# DAC_Test_PCB.net
KiCad netlist of a schematic drawn in EAGLE
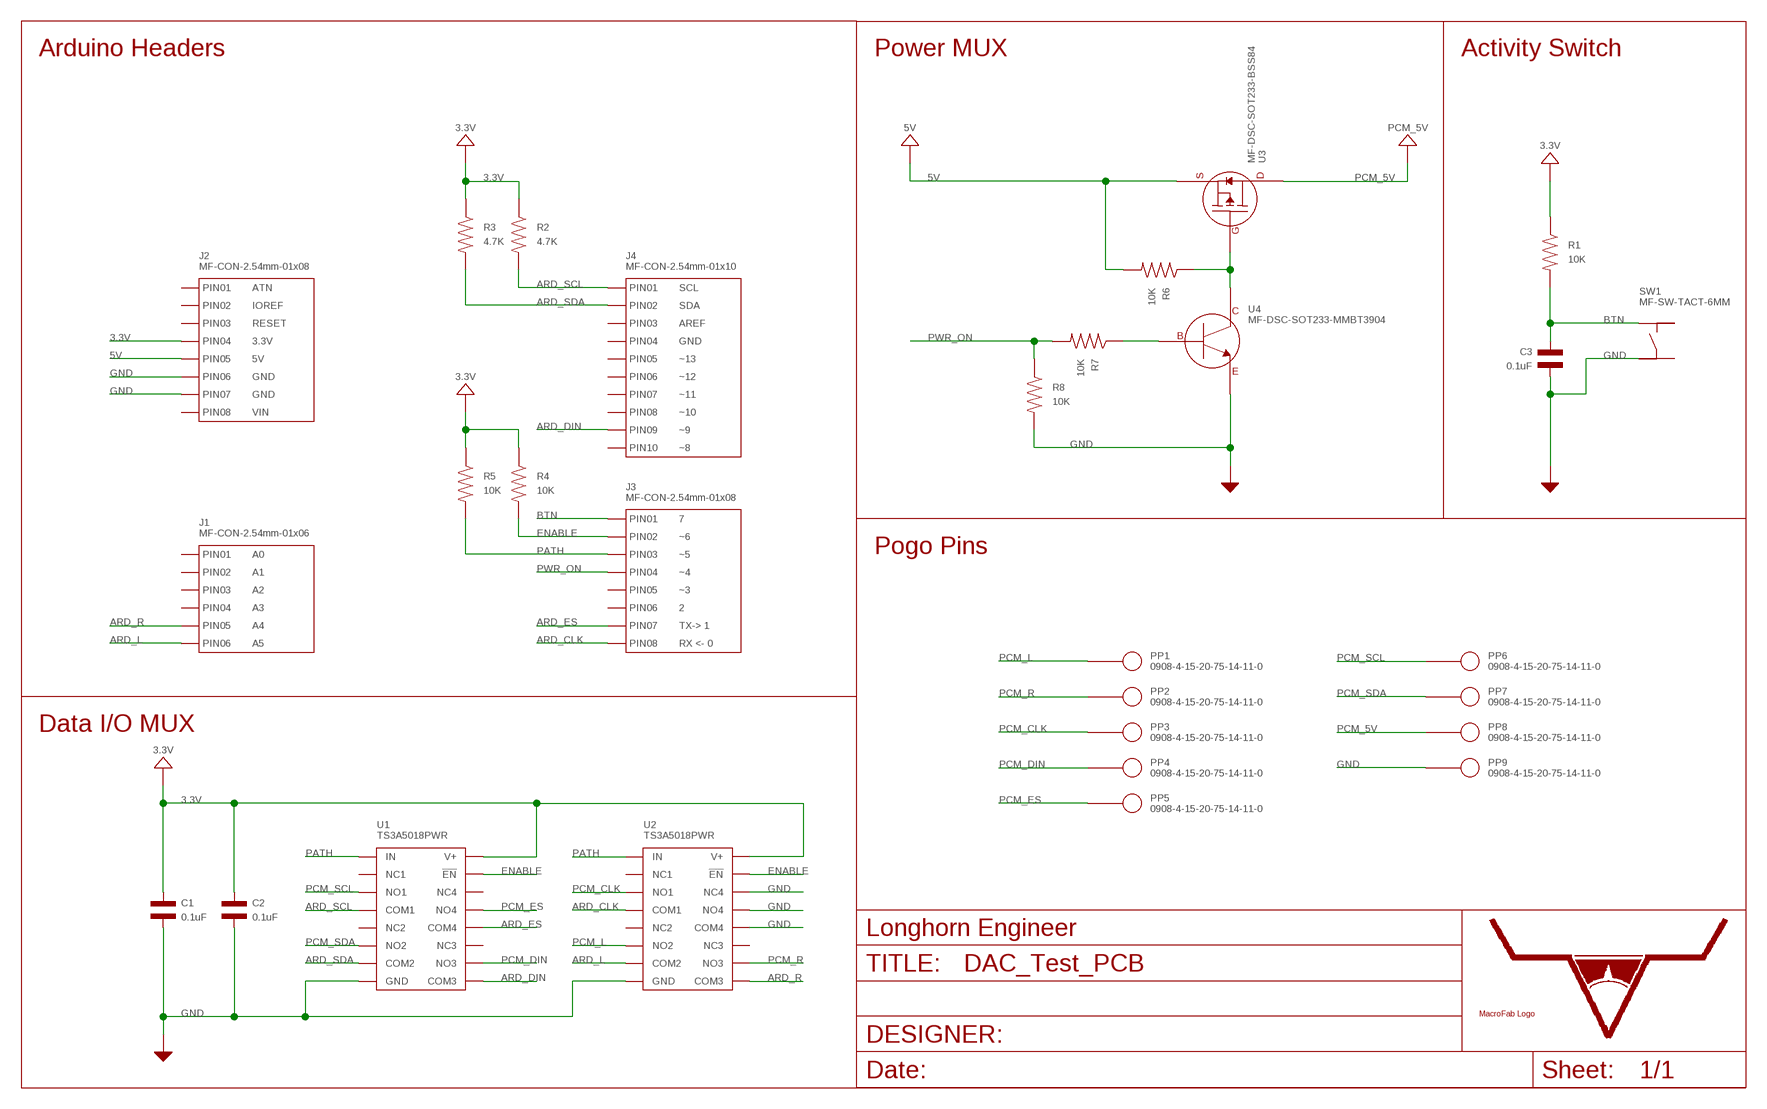
[diagram p0: schematic, sheet 1]

(export (version "E")
  (design (tool "Eeschema 10.0.6"))
  (components
    (comp (ref "C1")
      (value "0.1uF")
      (footprint "eagle-import:C0603")
      (libsource (lib "eagle-import") (part "CAPACITOR_NP_0603"))
    )
    (comp (ref "C2")
      (value "0.1uF")
      (footprint "eagle-import:C0603")
      (libsource (lib "eagle-import") (part "CAPACITOR_NP_0603"))
    )
    (comp (ref "C3")
      (value "0.1uF")
      (footprint "eagle-import:C0603")
      (libsource (lib "eagle-import") (part "CAPACITOR_NP_0603"))
    )
    (comp (ref "J1")
      (value "MF-CON-2.54mm-01x06")
      (footprint "eagle-import:PTH_2.54MM_01X06")
      (fields
        (field (name "HOUSEPART") "YES")
        (field (name "LABEL01") "A0")
        (field (name "LABEL02") "A1")
        (field (name "LABEL03") "A2")
        (field (name "LABEL04") "A3")
        (field (name "LABEL05") "A4")
        (field (name "LABEL06") "A5")
      )
      (libsource (lib "eagle-import") (part "CON_01X06_PTH_2.54MM"))
    )
    (comp (ref "J2")
      (value "MF-CON-2.54mm-01x08")
      (footprint "eagle-import:PTH_2.54MM_01X08")
      (fields
        (field (name "HOUSEPART") "YES")
        (field (name "LABEL01") "ATN")
        (field (name "LABEL02") "IOREF")
        (field (name "LABEL03") "RESET")
        (field (name "LABEL04") "3.3V")
        (field (name "LABEL05") "5V")
        (field (name "LABEL06") "GND")
        (field (name "LABEL07") "GND")
        (field (name "LABEL08") "VIN")
      )
      (libsource (lib "eagle-import") (part "CON_01X08_PTH_2.54MM"))
    )
    (comp (ref "J3")
      (value "MF-CON-2.54mm-01x08")
      (footprint "eagle-import:PTH_2.54MM_01X08")
      (fields
        (field (name "HOUSEPART") "YES")
        (field (name "LABEL01") "7")
        (field (name "LABEL02") "~6")
        (field (name "LABEL03") "~5")
        (field (name "LABEL04") "~4")
        (field (name "LABEL05") "~3")
        (field (name "LABEL06") "2")
        (field (name "LABEL07") "TX-> 1")
        (field (name "LABEL08") "RX <- 0")
      )
      (libsource (lib "eagle-import") (part "CON_01X08_PTH_2.54MM"))
    )
    (comp (ref "J4")
      (value "MF-CON-2.54mm-01x10")
      (footprint "eagle-import:PTH_2.54MM_01X10")
      (fields
        (field (name "HOUSEPART") "YES")
        (field (name "LABEL01") "SCL")
        (field (name "LABEL02") "SDA")
        (field (name "LABEL03") "AREF")
        (field (name "LABEL04") "GND")
        (field (name "LABEL05") "~13")
        (field (name "LABEL06") "~12")
        (field (name "LABEL07") "~11")
        (field (name "LABEL08") "~10")
        (field (name "LABEL09") "~9")
        (field (name "LABEL10") "~8")
      )
      (libsource (lib "eagle-import") (part "CON_01X10_PTH_2.54MM"))
    )
    (comp (ref "PP1")
      (value "0908-4-15-20-75-14-11-0")
      (footprint "eagle-import:0908-4-15-20-75-14-11-0")
      (libsource (lib "eagle-import") (part "POGO_PIN_0908-4-15-20-75-14-11-0"))
    )
    (comp (ref "PP2")
      (value "0908-4-15-20-75-14-11-0")
      (footprint "eagle-import:0908-4-15-20-75-14-11-0")
      (libsource (lib "eagle-import") (part "POGO_PIN_0908-4-15-20-75-14-11-0"))
    )
    (comp (ref "PP3")
      (value "0908-4-15-20-75-14-11-0")
      (footprint "eagle-import:0908-4-15-20-75-14-11-0")
      (libsource (lib "eagle-import") (part "POGO_PIN_0908-4-15-20-75-14-11-0"))
    )
    (comp (ref "PP4")
      (value "0908-4-15-20-75-14-11-0")
      (footprint "eagle-import:0908-4-15-20-75-14-11-0")
      (libsource (lib "eagle-import") (part "POGO_PIN_0908-4-15-20-75-14-11-0"))
    )
    (comp (ref "PP5")
      (value "0908-4-15-20-75-14-11-0")
      (footprint "eagle-import:0908-4-15-20-75-14-11-0")
      (libsource (lib "eagle-import") (part "POGO_PIN_0908-4-15-20-75-14-11-0"))
    )
    (comp (ref "PP6")
      (value "0908-4-15-20-75-14-11-0")
      (footprint "eagle-import:0908-4-15-20-75-14-11-0")
      (libsource (lib "eagle-import") (part "POGO_PIN_0908-4-15-20-75-14-11-0"))
    )
    (comp (ref "PP7")
      (value "0908-4-15-20-75-14-11-0")
      (footprint "eagle-import:0908-4-15-20-75-14-11-0")
      (libsource (lib "eagle-import") (part "POGO_PIN_0908-4-15-20-75-14-11-0"))
    )
    (comp (ref "PP8")
      (value "0908-4-15-20-75-14-11-0")
      (footprint "eagle-import:0908-4-15-20-75-14-11-0")
      (libsource (lib "eagle-import") (part "POGO_PIN_0908-4-15-20-75-14-11-0"))
    )
    (comp (ref "PP9")
      (value "0908-4-15-20-75-14-11-0")
      (footprint "eagle-import:0908-4-15-20-75-14-11-0")
      (libsource (lib "eagle-import") (part "POGO_PIN_0908-4-15-20-75-14-11-0"))
    )
    (comp (ref "R1")
      (value "10K")
      (footprint "eagle-import:R0603")
      (libsource (lib "eagle-import") (part "RESISTOR_0603"))
    )
    (comp (ref "R2")
      (value "4.7K")
      (footprint "eagle-import:R0603")
      (libsource (lib "eagle-import") (part "RESISTOR_0603"))
    )
    (comp (ref "R3")
      (value "4.7K")
      (footprint "eagle-import:R0603")
      (libsource (lib "eagle-import") (part "RESISTOR_0603"))
    )
    (comp (ref "R4")
      (value "10K")
      (footprint "eagle-import:R0603")
      (libsource (lib "eagle-import") (part "RESISTOR_0603"))
    )
    (comp (ref "R5")
      (value "10K")
      (footprint "eagle-import:R0603")
      (libsource (lib "eagle-import") (part "RESISTOR_0603"))
    )
    (comp (ref "R6")
      (value "10K")
      (footprint "eagle-import:R0603")
      (libsource (lib "eagle-import") (part "RESISTOR_0603"))
    )
    (comp (ref "R7")
      (value "10K")
      (footprint "eagle-import:R0603")
      (libsource (lib "eagle-import") (part "RESISTOR_0603"))
    )
    (comp (ref "R8")
      (value "10K")
      (footprint "eagle-import:R0603")
      (libsource (lib "eagle-import") (part "RESISTOR_0603"))
    )
    (comp (ref "SW1")
      (value "MF-SW-TACT-6MM")
      (footprint "eagle-import:TACT6MM")
      (fields (field (name "HOUSEPART") "YES"))
      (libsource (lib "eagle-import") (part "TACT_6MM"))
    )
    (comp (ref "U$8")
      (value "LHE_FRAME")
      (footprint "eagle-import:LHE_FRAME")
      (fields (field (name "DNAME") "Parker Dillmann") (field (name "REVNUM") "REV 1"))
      (libsource (lib "eagle-import") (part "LHE_FRAME"))
    )
    (comp (ref "U$9")
      (value "MF_LOGOLOGO_MEDIUM")
      (footprint "eagle-import:MF_LOGO_MEDIUM")
      (libsource (lib "eagle-import") (part "MF_LOGOLOGO_MEDIUM"))
    )
    (comp (ref "U1")
      (value "TS3A5018PWR")
      (footprint "eagle-import:TS3A5018_TTSOP-16")
      (libsource (lib "eagle-import") (part "TS3A5018PWR"))
    )
    (comp (ref "U2")
      (value "TS3A5018PWR")
      (footprint "eagle-import:TS3A5018_TTSOP-16")
      (libsource (lib "eagle-import") (part "TS3A5018PWR"))
    )
    (comp (ref "U3")
      (value "MF-DSC-SOT233-BSS84")
      (footprint "eagle-import:SOT-23-3")
      (fields (field (name "HOUSEPART") "YES"))
      (libsource (lib "eagle-import") (part "P-CHANNEL_FET_SOT-23-3_BSS84"))
    )
    (comp (ref "U4")
      (value "MF-DSC-SOT233-MMBT3904")
      (footprint "eagle-import:SOT-23-3")
      (fields (field (name "HOUSEPART") "YES"))
      (libsource (lib "eagle-import") (part "NPN_BJT_SOT-23-3MMBT3904"))
    )
  )
  (nets
    (net (code "1") (name "/ARD_CLK") (class "Default")
      (node (ref "J3") (pin "P$8") (pinfunction "PIN8_P$8") (pintype "bidirectional"))
      (node (ref "U2") (pin "4") (pinfunction "COM1_4") (pintype "bidirectional"))
    )
    (net (code "2") (name "/ARD_DIN") (class "Default")
      (node (ref "J4") (pin "P$9") (pinfunction "PIN9_P$9") (pintype "bidirectional"))
      (node (ref "U1") (pin "9") (pinfunction "COM3_9") (pintype "bidirectional"))
    )
    (net (code "3") (name "/ARD_ES") (class "Default")
      (node (ref "J3") (pin "P$7") (pinfunction "PIN7_P$7") (pintype "bidirectional"))
      (node (ref "U1") (pin "12") (pinfunction "COM4_12") (pintype "bidirectional"))
    )
    (net (code "4") (name "/ARD_L") (class "Default")
      (node (ref "J1") (pin "P$6") (pinfunction "PIN6_P$6") (pintype "bidirectional"))
      (node (ref "U2") (pin "7") (pinfunction "COM2_7") (pintype "bidirectional"))
    )
    (net (code "5") (name "/ARD_R") (class "Default")
      (node (ref "J1") (pin "P$5") (pinfunction "PIN5_P$5") (pintype "bidirectional"))
      (node (ref "U2") (pin "9") (pinfunction "COM3_9") (pintype "bidirectional"))
    )
    (net (code "6") (name "/ARD_SCL") (class "Default")
      (node (ref "J4") (pin "P$1") (pinfunction "PIN1_P$1") (pintype "bidirectional"))
      (node (ref "R2") (pin "P$2") (pinfunction "P$2_P$2") (pintype "passive"))
      (node (ref "U1") (pin "4") (pinfunction "COM1_4") (pintype "bidirectional"))
    )
    (net (code "7") (name "/ARD_SDA") (class "Default")
      (node (ref "J4") (pin "P$2") (pinfunction "PIN2_P$2") (pintype "bidirectional"))
      (node (ref "R3") (pin "P$2") (pinfunction "P$2_P$2") (pintype "passive"))
      (node (ref "U1") (pin "7") (pinfunction "COM2_7") (pintype "bidirectional"))
    )
    (net (code "8") (name "/BTN") (class "Default")
      (node (ref "C3") (pin "P$1") (pinfunction "P$1_P$1") (pintype "passive"))
      (node (ref "J3") (pin "P$1") (pinfunction "PIN1_P$1") (pintype "bidirectional"))
      (node (ref "R1") (pin "P$2") (pinfunction "P$2_P$2") (pintype "passive"))
      (node (ref "SW1") (pin "P$1") (pinfunction "P$1_P$1") (pintype "bidirectional"))
    )
    (net (code "9") (name "/ENABLE") (class "Default")
      (node (ref "J3") (pin "P$2") (pinfunction "PIN2_P$2") (pintype "bidirectional"))
      (node (ref "R4") (pin "P$2") (pinfunction "P$2_P$2") (pintype "passive"))
      (node (ref "U1") (pin "15") (pinfunction "EN'_15") (pintype "bidirectional"))
      (node (ref "U2") (pin "15") (pinfunction "EN'_15") (pintype "bidirectional"))
    )
    (net (code "10") (name "/PATH") (class "Default")
      (node (ref "J3") (pin "P$3") (pinfunction "PIN3_P$3") (pintype "bidirectional"))
      (node (ref "R5") (pin "P$2") (pinfunction "P$2_P$2") (pintype "passive"))
      (node (ref "U1") (pin "1") (pinfunction "IN_1") (pintype "bidirectional"))
      (node (ref "U2") (pin "1") (pinfunction "IN_1") (pintype "bidirectional"))
    )
    (net (code "11") (name "/PCM_CLK") (class "Default")
      (node (ref "PP3") (pin "P$1") (pinfunction "P$1_P$1") (pintype "bidirectional"))
      (node (ref "U2") (pin "3") (pinfunction "NO1_3") (pintype "bidirectional"))
    )
    (net (code "12") (name "/PCM_DIN") (class "Default")
      (node (ref "PP4") (pin "P$1") (pinfunction "P$1_P$1") (pintype "bidirectional"))
      (node (ref "U1") (pin "10") (pinfunction "NO3_10") (pintype "bidirectional"))
    )
    (net (code "13") (name "/PCM_ES") (class "Default")
      (node (ref "PP5") (pin "P$1") (pinfunction "P$1_P$1") (pintype "bidirectional"))
      (node (ref "U1") (pin "13") (pinfunction "NO4_13") (pintype "bidirectional"))
    )
    (net (code "14") (name "/PCM_L") (class "Default")
      (node (ref "PP1") (pin "P$1") (pinfunction "P$1_P$1") (pintype "bidirectional"))
      (node (ref "U2") (pin "6") (pinfunction "NO2_6") (pintype "bidirectional"))
    )
    (net (code "15") (name "/PCM_R") (class "Default")
      (node (ref "PP2") (pin "P$1") (pinfunction "P$1_P$1") (pintype "bidirectional"))
      (node (ref "U2") (pin "10") (pinfunction "NO3_10") (pintype "bidirectional"))
    )
    (net (code "16") (name "/PCM_SCL") (class "Default")
      (node (ref "PP6") (pin "P$1") (pinfunction "P$1_P$1") (pintype "bidirectional"))
      (node (ref "U1") (pin "3") (pinfunction "NO1_3") (pintype "bidirectional"))
    )
    (net (code "17") (name "/PCM_SDA") (class "Default")
      (node (ref "PP7") (pin "P$1") (pinfunction "P$1_P$1") (pintype "bidirectional"))
      (node (ref "U1") (pin "6") (pinfunction "NO2_6") (pintype "bidirectional"))
    )
    (net (code "18") (name "/PWR_ON") (class "Default")
      (node (ref "J3") (pin "P$4") (pinfunction "PIN4_P$4") (pintype "bidirectional"))
      (node (ref "R7") (pin "P$2") (pinfunction "P$2_P$2") (pintype "passive"))
      (node (ref "R8") (pin "P$1") (pinfunction "P$1_P$1") (pintype "passive"))
    )
    (net (code "19") (name "3.3V") (class "Default")
      (node (ref "C1") (pin "P$1") (pinfunction "P$1_P$1") (pintype "passive"))
      (node (ref "C2") (pin "P$1") (pinfunction "P$1_P$1") (pintype "passive"))
      (node (ref "J2") (pin "P$4") (pinfunction "PIN4_P$4") (pintype "bidirectional"))
      (node (ref "R1") (pin "P$1") (pinfunction "P$1_P$1") (pintype "passive"))
      (node (ref "R2") (pin "P$1") (pinfunction "P$1_P$1") (pintype "passive"))
      (node (ref "R3") (pin "P$1") (pinfunction "P$1_P$1") (pintype "passive"))
      (node (ref "R4") (pin "P$1") (pinfunction "P$1_P$1") (pintype "passive"))
      (node (ref "R5") (pin "P$1") (pinfunction "P$1_P$1") (pintype "passive"))
      (node (ref "U1") (pin "16") (pinfunction "V+_16") (pintype "bidirectional"))
      (node (ref "U2") (pin "16") (pinfunction "V+_16") (pintype "bidirectional"))
    )
    (net (code "20") (name "5V") (class "Default")
      (node (ref "J2") (pin "P$5") (pinfunction "PIN5_P$5") (pintype "bidirectional"))
      (node (ref "R6") (pin "P$2") (pinfunction "P$2_P$2") (pintype "passive"))
      (node (ref "U3") (pin "P$2") (pinfunction "SOURCE_P$2") (pintype "bidirectional"))
    )
    (net (code "21") (name "GND_RAIL") (class "Default")
      (node (ref "C1") (pin "P$2") (pinfunction "P$2_P$2") (pintype "passive"))
      (node (ref "C2") (pin "P$2") (pinfunction "P$2_P$2") (pintype "passive"))
      (node (ref "C3") (pin "P$2") (pinfunction "P$2_P$2") (pintype "passive"))
      (node (ref "J2") (pin "P$6") (pinfunction "PIN6_P$6") (pintype "bidirectional"))
      (node (ref "J2") (pin "P$7") (pinfunction "PIN7_P$7") (pintype "bidirectional"))
      (node (ref "PP9") (pin "P$1") (pinfunction "P$1_P$1") (pintype "bidirectional"))
      (node (ref "R8") (pin "P$2") (pinfunction "P$2_P$2") (pintype "passive"))
      (node (ref "SW1") (pin "P$3") (pinfunction "P$3_P$3") (pintype "bidirectional"))
      (node (ref "U1") (pin "8") (pinfunction "GND_8") (pintype "bidirectional"))
      (node (ref "U2") (pin "12") (pinfunction "COM4_12") (pintype "bidirectional"))
      (node (ref "U2") (pin "13") (pinfunction "NO4_13") (pintype "bidirectional"))
      (node (ref "U2") (pin "14") (pinfunction "NC4_14") (pintype "bidirectional"))
      (node (ref "U2") (pin "8") (pinfunction "GND_8") (pintype "bidirectional"))
      (node (ref "U4") (pin "P$2") (pinfunction "EMITTER_P$2") (pintype "bidirectional"))
    )
    (net (code "22") (name "Net-(U3-GATE)") (class "Default")
      (node (ref "R6") (pin "P$1") (pinfunction "P$1_P$1") (pintype "passive"))
      (node (ref "U3") (pin "P$1") (pinfunction "GATE_P$1") (pintype "bidirectional"))
      (node (ref "U4") (pin "P$3") (pinfunction "COLLECTOR_P$3") (pintype "bidirectional"))
    )
    (net (code "23") (name "Net-(U4-BASE)") (class "Default")
      (node (ref "R7") (pin "P$1") (pinfunction "P$1_P$1") (pintype "passive"))
      (node (ref "U4") (pin "P$1") (pinfunction "BASE_P$1") (pintype "bidirectional"))
    )
    (net (code "24") (name "PCM_5V") (class "Default")
      (node (ref "PP8") (pin "P$1") (pinfunction "P$1_P$1") (pintype "bidirectional"))
      (node (ref "U3") (pin "P$3") (pinfunction "DRAIN_P$3") (pintype "bidirectional"))
    )
    (net (code "25") (name "unconnected-(J1-PIN1-PadP$1)") (class "Default")
      (node (ref "J1") (pin "P$1") (pinfunction "PIN1_P$1") (pintype "bidirectional"))
    )
    (net (code "26") (name "unconnected-(J1-PIN2-PadP$2)") (class "Default")
      (node (ref "J1") (pin "P$2") (pinfunction "PIN2_P$2") (pintype "bidirectional"))
    )
    (net (code "27") (name "unconnected-(J1-PIN3-PadP$3)") (class "Default")
      (node (ref "J1") (pin "P$3") (pinfunction "PIN3_P$3") (pintype "bidirectional"))
    )
    (net (code "28") (name "unconnected-(J1-PIN4-PadP$4)") (class "Default")
      (node (ref "J1") (pin "P$4") (pinfunction "PIN4_P$4") (pintype "bidirectional"))
    )
    (net (code "29") (name "unconnected-(J2-PIN1-PadP$1)") (class "Default")
      (node (ref "J2") (pin "P$1") (pinfunction "PIN1_P$1") (pintype "bidirectional"))
    )
    (net (code "30") (name "unconnected-(J2-PIN2-PadP$2)") (class "Default")
      (node (ref "J2") (pin "P$2") (pinfunction "PIN2_P$2") (pintype "bidirectional"))
    )
    (net (code "31") (name "unconnected-(J2-PIN3-PadP$3)") (class "Default")
      (node (ref "J2") (pin "P$3") (pinfunction "PIN3_P$3") (pintype "bidirectional"))
    )
    (net (code "32") (name "unconnected-(J2-PIN8-PadP$8)") (class "Default")
      (node (ref "J2") (pin "P$8") (pinfunction "PIN8_P$8") (pintype "bidirectional"))
    )
    (net (code "33") (name "unconnected-(J3-PIN5-PadP$5)") (class "Default")
      (node (ref "J3") (pin "P$5") (pinfunction "PIN5_P$5") (pintype "bidirectional"))
    )
    (net (code "34") (name "unconnected-(J3-PIN6-PadP$6)") (class "Default")
      (node (ref "J3") (pin "P$6") (pinfunction "PIN6_P$6") (pintype "bidirectional"))
    )
    (net (code "35") (name "unconnected-(J4-PIN3-PadP$3)") (class "Default")
      (node (ref "J4") (pin "P$3") (pinfunction "PIN3_P$3") (pintype "bidirectional"))
    )
    (net (code "36") (name "unconnected-(J4-PIN4-PadP$4)") (class "Default")
      (node (ref "J4") (pin "P$4") (pinfunction "PIN4_P$4") (pintype "bidirectional"))
    )
    (net (code "37") (name "unconnected-(J4-PIN5-PadP$5)") (class "Default")
      (node (ref "J4") (pin "P$5") (pinfunction "PIN5_P$5") (pintype "bidirectional"))
    )
    (net (code "38") (name "unconnected-(J4-PIN6-PadP$6)") (class "Default")
      (node (ref "J4") (pin "P$6") (pinfunction "PIN6_P$6") (pintype "bidirectional"))
    )
    (net (code "39") (name "unconnected-(J4-PIN7-PadP$7)") (class "Default")
      (node (ref "J4") (pin "P$7") (pinfunction "PIN7_P$7") (pintype "bidirectional"))
    )
    (net (code "40") (name "unconnected-(J4-PIN8-PadP$8)") (class "Default")
      (node (ref "J4") (pin "P$8") (pinfunction "PIN8_P$8") (pintype "bidirectional"))
    )
    (net (code "41") (name "unconnected-(J4-PIN10-PadP$10)") (class "Default")
      (node (ref "J4") (pin "P$10") (pinfunction "PIN10_P$10") (pintype "bidirectional"))
    )
    (net (code "42") (name "unconnected-(SW1-PadP$2)") (class "Default")
      (node (ref "SW1") (pin "P$2") (pinfunction "P$2_P$2") (pintype "bidirectional"))
    )
    (net (code "43") (name "unconnected-(SW1-PadP$4)") (class "Default")
      (node (ref "SW1") (pin "P$4") (pinfunction "P$4_P$4") (pintype "bidirectional"))
    )
    (net (code "44") (name "unconnected-(U1-NC1-Pad2)") (class "Default")
      (node (ref "U1") (pin "2") (pinfunction "NC1_2") (pintype "bidirectional"))
    )
    (net (code "45") (name "unconnected-(U1-NC2-Pad5)") (class "Default")
      (node (ref "U1") (pin "5") (pinfunction "NC2_5") (pintype "bidirectional"))
    )
    (net (code "46") (name "unconnected-(U1-NC3-Pad11)") (class "Default")
      (node (ref "U1") (pin "11") (pinfunction "NC3_11") (pintype "bidirectional"))
    )
    (net (code "47") (name "unconnected-(U1-NC4-Pad14)") (class "Default")
      (node (ref "U1") (pin "14") (pinfunction "NC4_14") (pintype "bidirectional"))
    )
    (net (code "48") (name "unconnected-(U2-NC1-Pad2)") (class "Default")
      (node (ref "U2") (pin "2") (pinfunction "NC1_2") (pintype "bidirectional"))
    )
    (net (code "49") (name "unconnected-(U2-NC2-Pad5)") (class "Default")
      (node (ref "U2") (pin "5") (pinfunction "NC2_5") (pintype "bidirectional"))
    )
    (net (code "50") (name "unconnected-(U2-NC3-Pad11)") (class "Default")
      (node (ref "U2") (pin "11") (pinfunction "NC3_11") (pintype "bidirectional"))
    )
  )
)
